# v1.net
KiCad netlist of a schematic drawn in EAGLE
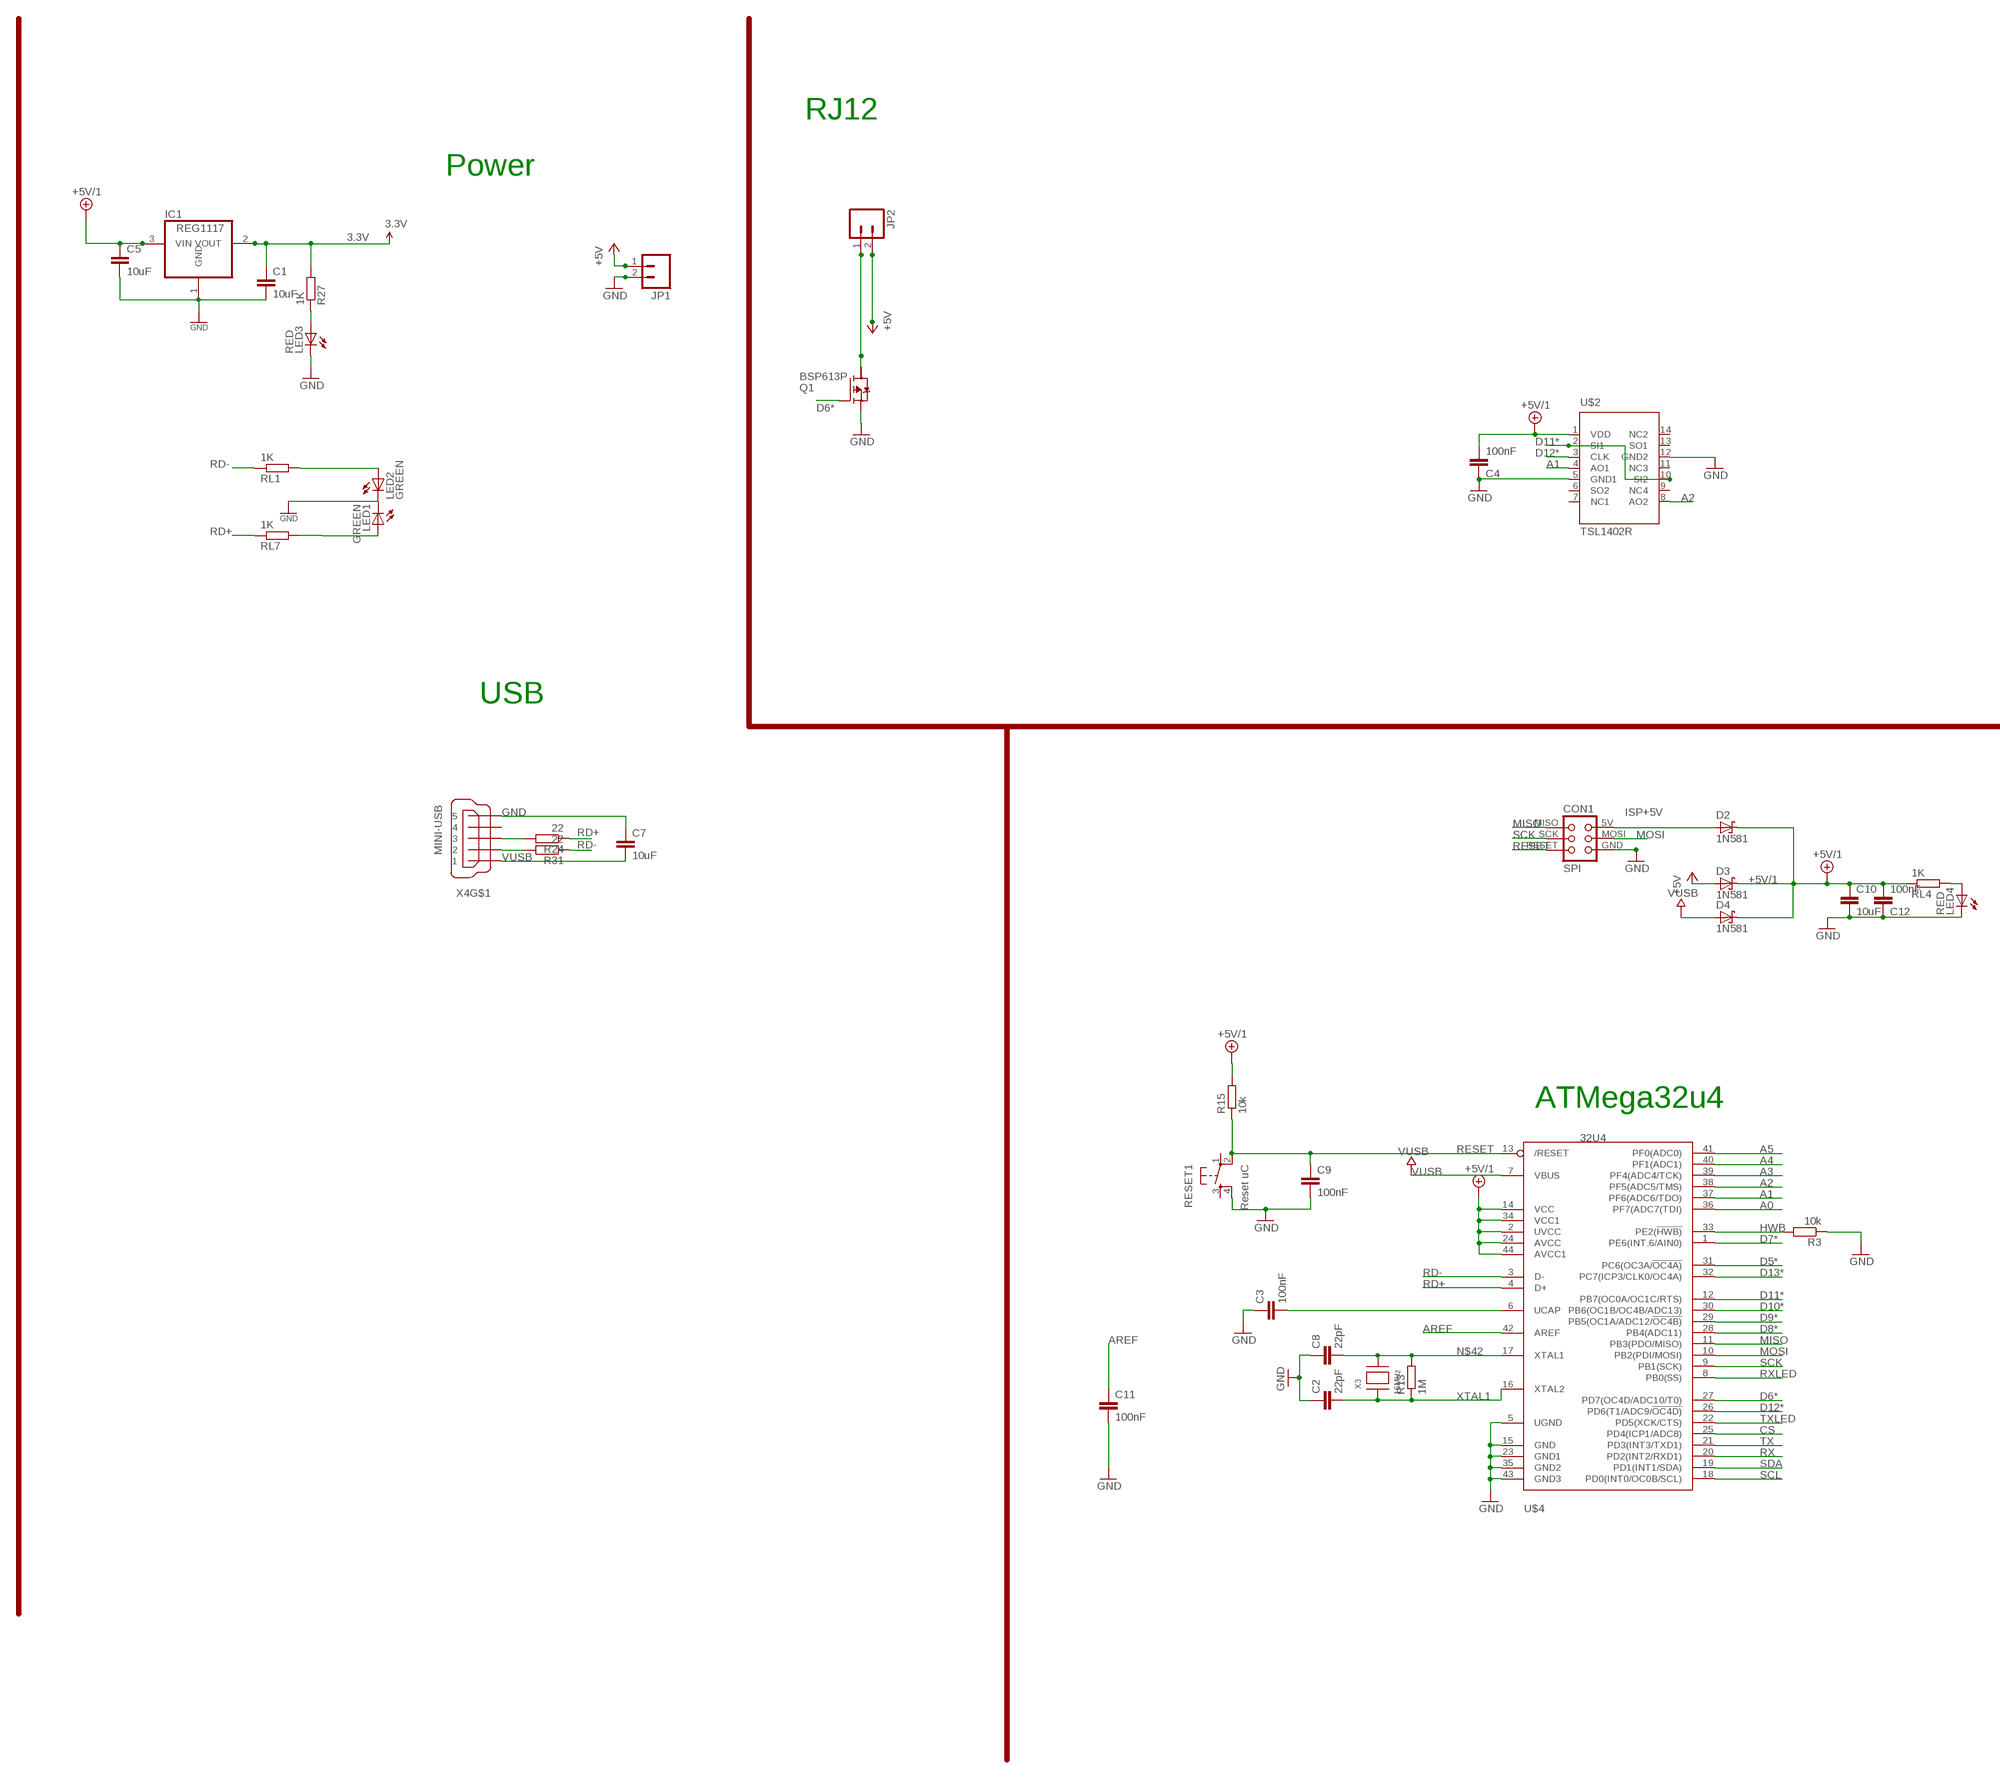
[diagram p0: schematic, sheet 1, part 1 of 2]
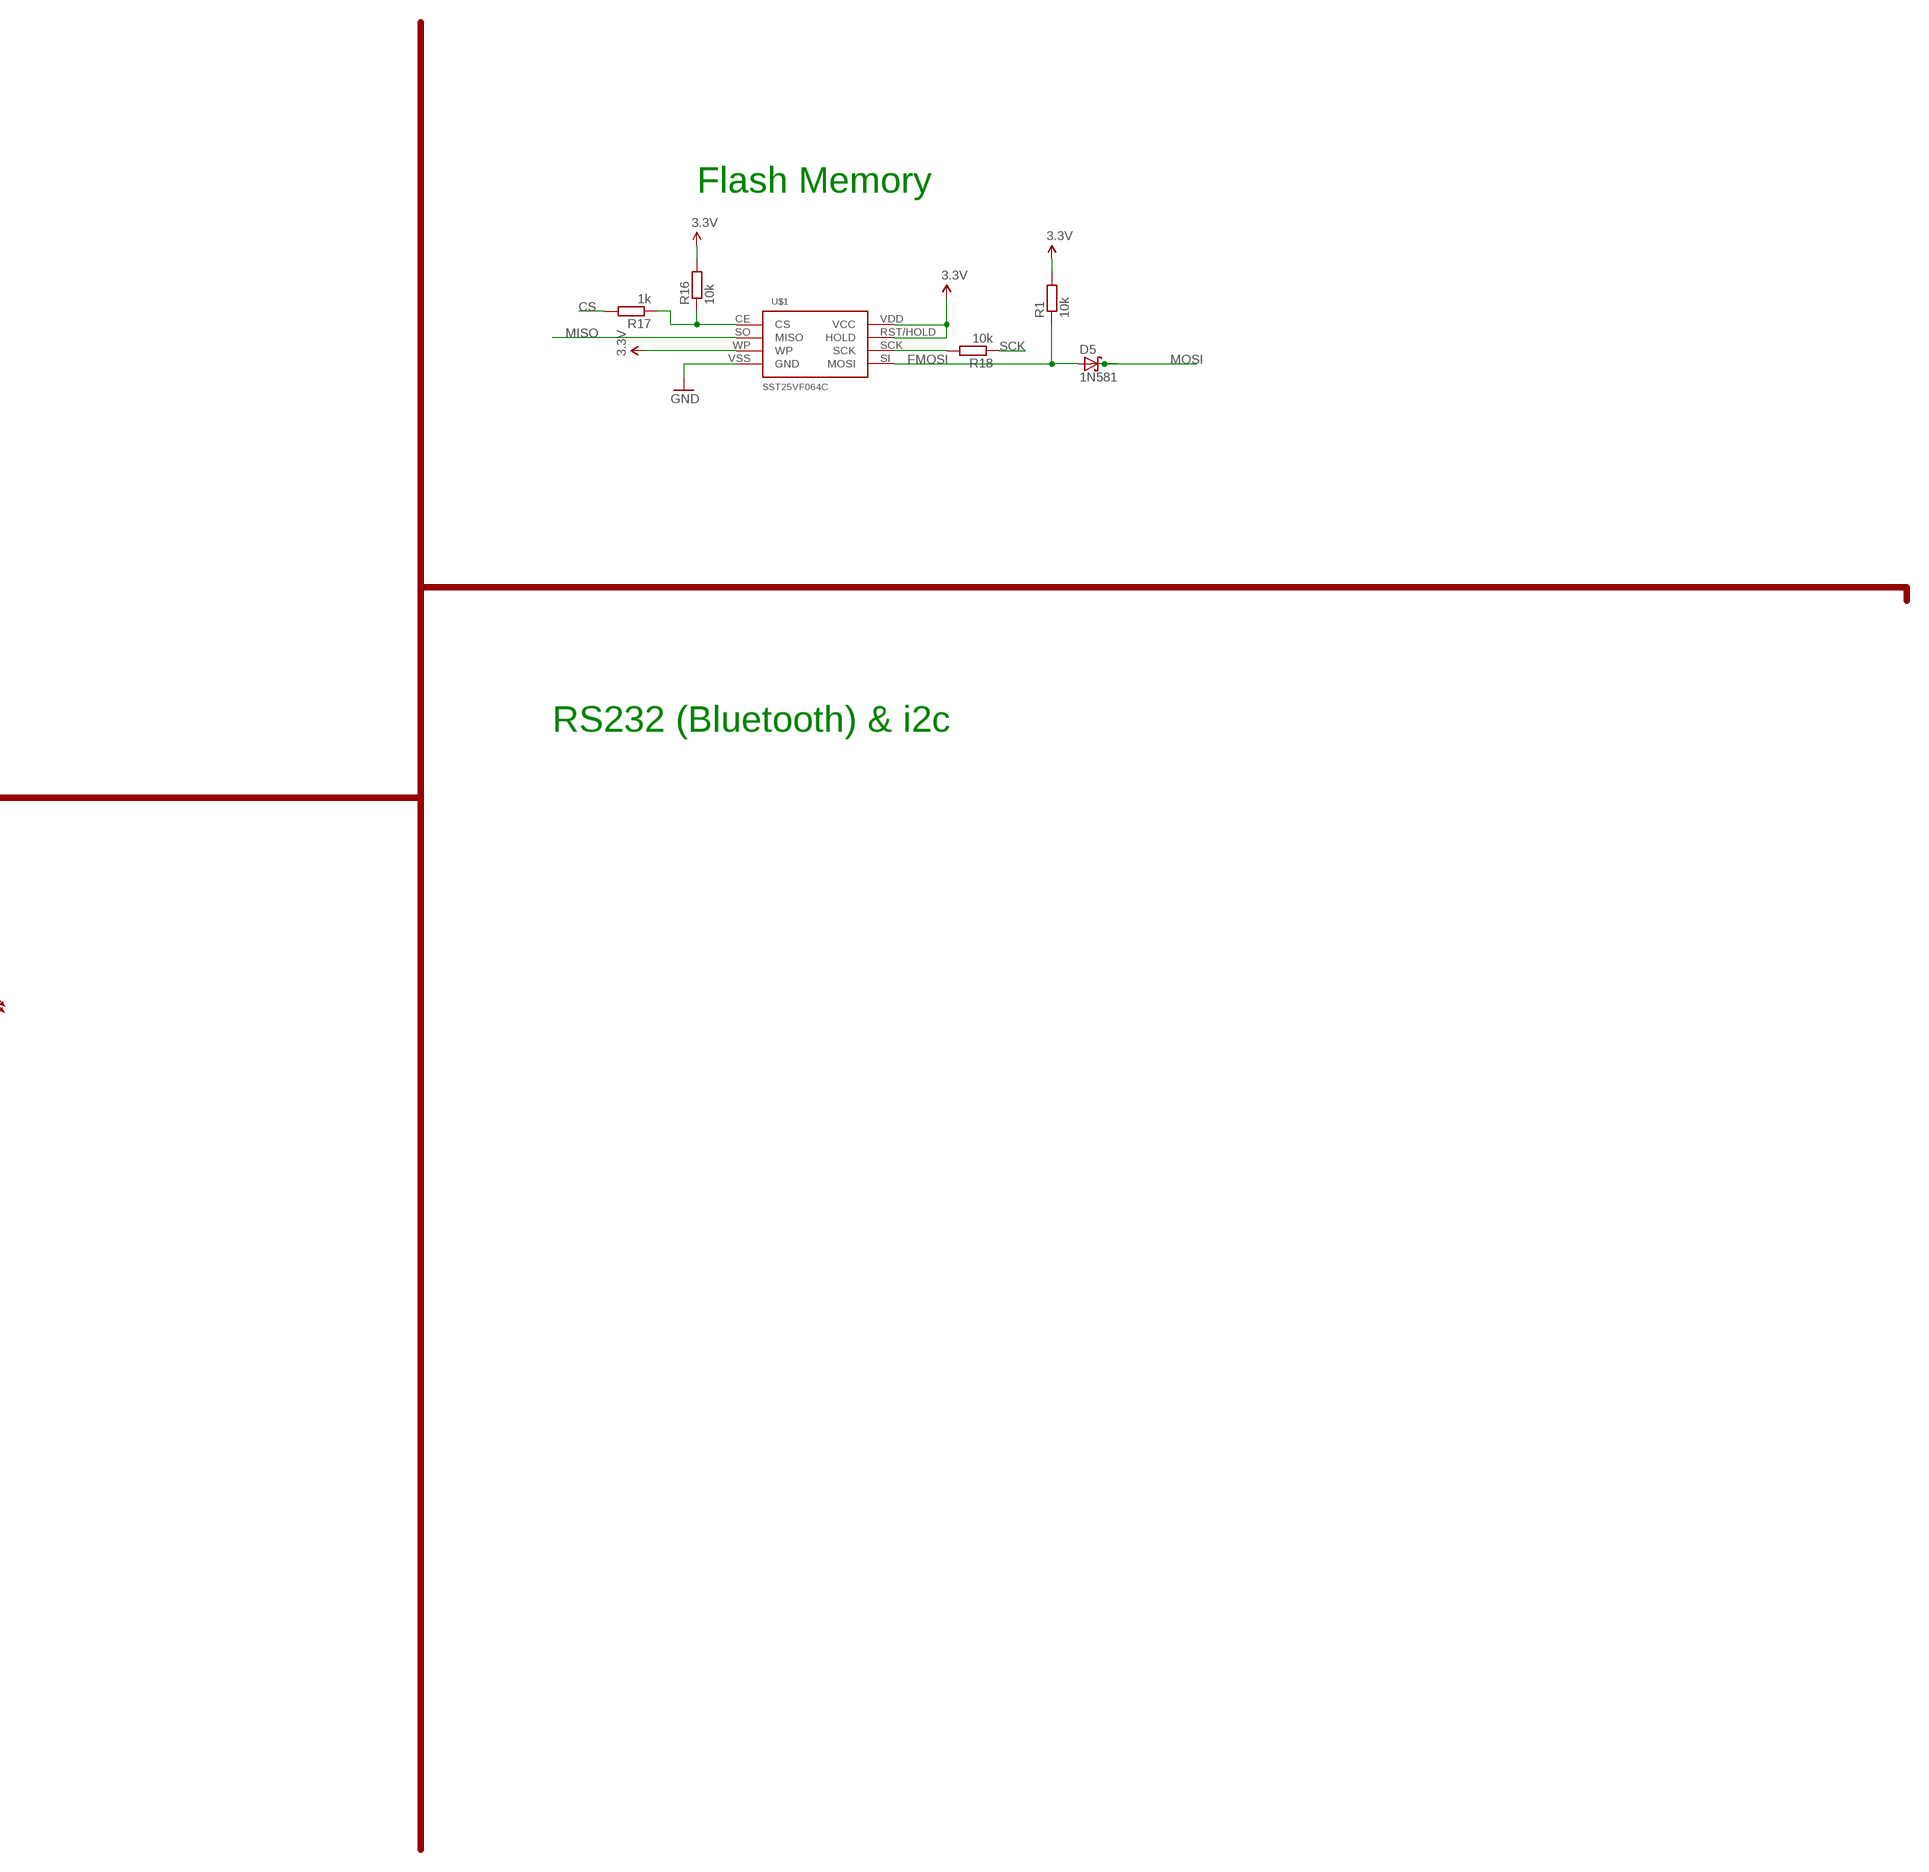
[diagram p1: schematic, sheet 1, part 2 of 2]

(export (version "E")
  (design (tool "Eeschema 10.0.6"))
  (components
    (comp (ref "C1")
      (value "10uF")
      (footprint "eagle-import:C1206")
      (libsource (lib "eagle-import") (part "C-EUC1206"))
    )
    (comp (ref "C2")
      (value "22pF")
      (footprint "eagle-import:C1206")
      (libsource (lib "eagle-import") (part "C-EUC1206"))
    )
    (comp (ref "C3")
      (value "100nF")
      (footprint "eagle-import:C1206")
      (libsource (lib "eagle-import") (part "C-EUC1206"))
    )
    (comp (ref "C4")
      (value "100nF")
      (footprint "eagle-import:C1206")
      (libsource (lib "eagle-import") (part "C-EUC1206"))
    )
    (comp (ref "C5")
      (value "10uF")
      (footprint "eagle-import:C1206")
      (libsource (lib "eagle-import") (part "C-EUC1206"))
    )
    (comp (ref "C7")
      (value "10uF")
      (footprint "eagle-import:C1206")
      (libsource (lib "eagle-import") (part "C-EUC1206"))
    )
    (comp (ref "C8")
      (value "22pF")
      (footprint "eagle-import:C1206")
      (libsource (lib "eagle-import") (part "C-EUC1206"))
    )
    (comp (ref "C9")
      (value "100nF")
      (footprint "eagle-import:C1206")
      (libsource (lib "eagle-import") (part "C-EUC1206"))
    )
    (comp (ref "C10")
      (value "10uF")
      (footprint "eagle-import:C1206")
      (libsource (lib "eagle-import") (part "C-EUC1206"))
    )
    (comp (ref "C11")
      (value "100nF")
      (footprint "eagle-import:C1206")
      (libsource (lib "eagle-import") (part "C-EUC1206"))
    )
    (comp (ref "C12")
      (value "100nF")
      (footprint "eagle-import:C1206")
      (libsource (lib "eagle-import") (part "C-EUC1206"))
    )
    (comp (ref "CON1")
      (value "SPI")
      (footprint "eagle-import:TC2030-MCP-NL")
      (libsource (lib "eagle-import") (part "TINYISPT"))
    )
    (comp (ref "D2")
      (value "1N581")
      (footprint "eagle-import:LED-1206")
      (libsource (lib "eagle-import") (part "1N581D1206"))
    )
    (comp (ref "D3")
      (value "1N581")
      (footprint "eagle-import:LED-1206")
      (libsource (lib "eagle-import") (part "1N581D1206"))
    )
    (comp (ref "D4")
      (value "1N581")
      (footprint "eagle-import:LED-1206")
      (libsource (lib "eagle-import") (part "1N581D1206"))
    )
    (comp (ref "D5")
      (value "1N581")
      (footprint "eagle-import:LED-1206")
      (libsource (lib "eagle-import") (part "1N581D1206"))
    )
    (comp (ref "IC1")
      (value "REG1117")
      (footprint "eagle-import:SOT223")
      (libsource (lib "eagle-import") (part "REG1117"))
    )
    (comp (ref "JP1")
      (value "M02LOCK_LONGPADS")
      (footprint "eagle-import:1X02_LOCK_LONGPADS")
      (libsource (lib "eagle-import") (part "M02LOCK_LONGPADS"))
    )
    (comp (ref "JP2")
      (value "M02LOCK_LONGPADS")
      (footprint "eagle-import:1X02_LOCK_LONGPADS")
      (libsource (lib "eagle-import") (part "M02LOCK_LONGPADS"))
    )
    (comp (ref "LED1")
      (value "GREEN")
      (footprint "eagle-import:CHIP-LED0805")
      (libsource (lib "eagle-import") (part "LEDCHIP-LED0805"))
    )
    (comp (ref "LED2")
      (value "GREEN")
      (footprint "eagle-import:CHIP-LED0805")
      (libsource (lib "eagle-import") (part "LEDCHIP-LED0805"))
    )
    (comp (ref "LED3")
      (value "RED")
      (footprint "eagle-import:CHIP-LED0805")
      (libsource (lib "eagle-import") (part "LEDCHIP-LED0805"))
    )
    (comp (ref "LED4")
      (value "RED")
      (footprint "eagle-import:CHIP-LED0805")
      (libsource (lib "eagle-import") (part "LEDCHIP-LED0805"))
    )
    (comp (ref "Q1")
      (value "BSP613P")
      (footprint "eagle-import:PG-SOT-223")
      (libsource (lib "eagle-import") (part "BSP613P"))
    )
    (comp (ref "R1")
      (value "10k")
      (footprint "eagle-import:R1206")
      (libsource (lib "eagle-import") (part "R-EU_R1206"))
    )
    (comp (ref "R3")
      (value "10k")
      (footprint "eagle-import:M0805")
      (libsource (lib "eagle-import") (part "resistor_R-EU_M0805"))
    )
    (comp (ref "R13")
      (value "1M")
      (footprint "eagle-import:R1206")
      (libsource (lib "eagle-import") (part "R-EU_R1206"))
    )
    (comp (ref "R15")
      (value "10k")
      (footprint "eagle-import:M0805")
      (libsource (lib "eagle-import") (part "resistor_R-EU_M0805"))
    )
    (comp (ref "R16")
      (value "10k")
      (footprint "eagle-import:R1206")
      (libsource (lib "eagle-import") (part "R-EU_R1206"))
    )
    (comp (ref "R17")
      (value "1k")
      (footprint "eagle-import:R0805")
      (libsource (lib "eagle-import") (part "R-EU_R0805"))
    )
    (comp (ref "R18")
      (value "10k")
      (footprint "eagle-import:R1206")
      (libsource (lib "eagle-import") (part "R-EU_R1206"))
    )
    (comp (ref "R24")
      (value "22")
      (footprint "eagle-import:M1206")
      (libsource (lib "eagle-import") (part "resistor_R-EU_M1206"))
    )
    (comp (ref "R27")
      (value "1K")
      (footprint "eagle-import:R0805")
      (libsource (lib "eagle-import") (part "R-EU_R0805"))
    )
    (comp (ref "R31")
      (value "22")
      (footprint "eagle-import:M1206")
      (libsource (lib "eagle-import") (part "resistor_R-EU_M1206"))
    )
    (comp (ref "RESET1")
      (value "Reset uC")
      (footprint "eagle-import:TACTILE_SWITCH_SMD")
      (libsource (lib "eagle-import") (part "TAC_SWITCHSMD"))
    )
    (comp (ref "RL1")
      (value "1K")
      (footprint "eagle-import:R0805")
      (libsource (lib "eagle-import") (part "R-EU_R0805"))
    )
    (comp (ref "RL4")
      (value "1K")
      (footprint "eagle-import:R0805")
      (libsource (lib "eagle-import") (part "resistor_R-EU_R0805"))
    )
    (comp (ref "RL7")
      (value "1K")
      (footprint "eagle-import:R0805")
      (libsource (lib "eagle-import") (part "R-EU_R0805"))
    )
    (comp (ref "U$1")
      (value "SST25VF064C")
      (footprint "eagle-import:SOIC_8-LEAD")
      (libsource (lib "eagle-import") (part "SST25VF064C"))
    )
    (comp (ref "U$2")
      (value "TSL1402R")
      (footprint "eagle-import:DIL14")
      (libsource (lib "eagle-import") (part "TSL1402R"))
    )
    (comp (ref "U$4")
      (value "32U4")
      (footprint "eagle-import:TQFP44")
      (libsource (lib "eagle-import") (part "ATMEGA32U4-AU"))
    )
    (comp (ref "X3")
      (value "16MHz")
      (footprint "eagle-import:NX6035")
      (libsource (lib "eagle-import") (part "XTALNX6035"))
    )
    (comp (ref "X4")
      (value "MINI-USB")
      (footprint "eagle-import:32005-201")
      (libsource (lib "eagle-import") (part "MINI-USB-SCHIELD-32005-201"))
    )
  )
  (nets
    (net (code "1") (name "+5V") (class "Default")
      (node (ref "D3") (pin "A") (pinfunction "A_A") (pintype "passive"))
      (node (ref "JP1") (pin "1") (pinfunction "1_1") (pintype "passive"))
      (node (ref "JP2") (pin "2") (pinfunction "2_2") (pintype "passive"))
    )
    (net (code "2") (name "+5V{slash}1") (class "Default")
      (node (ref "C10") (pin "1") (pinfunction "1_1") (pintype "passive"))
      (node (ref "C12") (pin "2") (pinfunction "2_2") (pintype "passive"))
      (node (ref "C4") (pin "2") (pinfunction "2_2") (pintype "passive"))
      (node (ref "C5") (pin "1") (pinfunction "1_1") (pintype "passive"))
      (node (ref "D2") (pin "C") (pinfunction "C_C") (pintype "passive"))
      (node (ref "D3") (pin "C") (pinfunction "C_C") (pintype "passive"))
      (node (ref "D4") (pin "C") (pinfunction "C_C") (pintype "passive"))
      (node (ref "IC1") (pin "3") (pinfunction "VIN_3") (pintype "input"))
      (node (ref "R15") (pin "2") (pinfunction "2_2") (pintype "passive"))
      (node (ref "RL4") (pin "1") (pinfunction "1_1") (pintype "passive"))
      (node (ref "U$2") (pin "1") (pinfunction "VDD_1") (pintype "power_in"))
      (node (ref "U$4") (pin "14") (pinfunction "VCC_14") (pintype "bidirectional"))
      (node (ref "U$4") (pin "2") (pinfunction "UVCC_2") (pintype "bidirectional"))
      (node (ref "U$4") (pin "24") (pinfunction "AVCC_24") (pintype "bidirectional"))
      (node (ref "U$4") (pin "34") (pinfunction "VCC1_34") (pintype "bidirectional"))
      (node (ref "U$4") (pin "44") (pinfunction "AVCC1_44") (pintype "bidirectional"))
    )
    (net (code "3") (name "/A0") (class "Default")
      (node (ref "U$4") (pin "36") (pinfunction "PF7(ADC7(TDI)_36") (pintype "bidirectional"))
    )
    (net (code "4") (name "/A1") (class "Default")
      (node (ref "U$2") (pin "4") (pinfunction "AO1_4") (pintype "output"))
      (node (ref "U$4") (pin "37") (pinfunction "PF6(ADC6/TDO)_37") (pintype "bidirectional"))
    )
    (net (code "5") (name "/A2") (class "Default")
      (node (ref "U$2") (pin "8") (pinfunction "AO2_8") (pintype "output"))
      (node (ref "U$4") (pin "38") (pinfunction "PF5(ADC5/TMS)_38") (pintype "bidirectional"))
    )
    (net (code "6") (name "/A3") (class "Default")
      (node (ref "U$4") (pin "39") (pinfunction "PF4(ADC4/TCK)_39") (pintype "bidirectional"))
    )
    (net (code "7") (name "/A4") (class "Default")
      (node (ref "U$4") (pin "40") (pinfunction "PF1(ADC1)_40") (pintype "bidirectional"))
    )
    (net (code "8") (name "/A5") (class "Default")
      (node (ref "U$4") (pin "41") (pinfunction "PF0(ADC0)_41") (pintype "bidirectional"))
    )
    (net (code "9") (name "/AREF") (class "Default")
      (node (ref "C11") (pin "1") (pinfunction "1_1") (pintype "passive"))
      (node (ref "U$4") (pin "42") (pinfunction "AREF_42") (pintype "bidirectional"))
    )
    (net (code "10") (name "/CS") (class "Default")
      (node (ref "R17") (pin "2") (pinfunction "2_2") (pintype "passive"))
      (node (ref "U$4") (pin "25") (pinfunction "PD4(ICP1/ADC8)_25") (pintype "bidirectional"))
    )
    (net (code "11") (name "/D5*") (class "Default")
      (node (ref "U$4") (pin "31") (pinfunction "PC6(OC3A/~{OC4A})_31") (pintype "bidirectional"))
    )
    (net (code "12") (name "/D6*") (class "Default")
      (node (ref "Q1") (pin "1") (pinfunction "G_1") (pintype "passive"))
      (node (ref "U$4") (pin "27") (pinfunction "PD7(OC4D/ADC10/T0)_27") (pintype "bidirectional"))
    )
    (net (code "13") (name "/D7*") (class "Default")
      (node (ref "U$4") (pin "1") (pinfunction "PE6(INT.6/AIN0)_1") (pintype "bidirectional"))
    )
    (net (code "14") (name "/D8*") (class "Default")
      (node (ref "U$4") (pin "28") (pinfunction "PB4(ADC11)_28") (pintype "bidirectional"))
    )
    (net (code "15") (name "/D9*") (class "Default")
      (node (ref "U$4") (pin "29") (pinfunction "PB5(OC1A/ADC12/~{OC4B})_29") (pintype "bidirectional"))
    )
    (net (code "16") (name "/D10*") (class "Default")
      (node (ref "U$4") (pin "30") (pinfunction "PB6(OC1B/OC4B/ADC13)_30") (pintype "bidirectional"))
    )
    (net (code "17") (name "/D11*") (class "Default")
      (node (ref "U$2") (pin "10") (pinfunction "SI2_10") (pintype "input"))
      (node (ref "U$2") (pin "2") (pinfunction "SI1_2") (pintype "input"))
      (node (ref "U$4") (pin "12") (pinfunction "PB7(OC0A/OC1C/RTS)_12") (pintype "bidirectional"))
    )
    (net (code "18") (name "/D12*") (class "Default")
      (node (ref "U$2") (pin "3") (pinfunction "CLK_3") (pintype "input"))
      (node (ref "U$4") (pin "26") (pinfunction "PD6(T1/ADC9/~{OC4D})_26") (pintype "bidirectional"))
    )
    (net (code "19") (name "/D13*") (class "Default")
      (node (ref "U$4") (pin "32") (pinfunction "PC7(ICP3/CLK0/OC4A)_32") (pintype "bidirectional"))
    )
    (net (code "20") (name "/FMOSI") (class "Default")
      (node (ref "D5") (pin "A") (pinfunction "A_A") (pintype "passive"))
      (node (ref "R1") (pin "1") (pinfunction "1_1") (pintype "passive"))
      (node (ref "U$1") (pin "SI") (pinfunction "MOSI_SI") (pintype "bidirectional"))
    )
    (net (code "21") (name "/HWB") (class "Default")
      (node (ref "R3") (pin "2") (pinfunction "2_2") (pintype "passive"))
      (node (ref "U$4") (pin "33") (pinfunction "PE2(~{HWB})_33") (pintype "bidirectional"))
    )
    (net (code "22") (name "/ISP+5V") (class "Default")
      (node (ref "CON1") (pin "5V") (pinfunction "VCC_5V") (pintype "passive"))
      (node (ref "D2") (pin "A") (pinfunction "A_A") (pintype "passive"))
    )
    (net (code "23") (name "/MISO") (class "Default")
      (node (ref "CON1") (pin "MISO") (pinfunction "MISO_MISO") (pintype "passive"))
      (node (ref "U$1") (pin "SO") (pinfunction "MISO_SO") (pintype "bidirectional"))
      (node (ref "U$4") (pin "11") (pinfunction "PB3(PDO/MISO)_11") (pintype "bidirectional"))
    )
    (net (code "24") (name "/MOSI") (class "Default")
      (node (ref "CON1") (pin "MOSI") (pinfunction "MOSI_MOSI") (pintype "passive"))
      (node (ref "D5") (pin "C") (pinfunction "C_C") (pintype "passive"))
      (node (ref "U$4") (pin "10") (pinfunction "PB2(PDI/MOSI)_10") (pintype "bidirectional"))
    )
    (net (code "25") (name "/N$42") (class "Default")
      (node (ref "C8") (pin "2") (pinfunction "2_2") (pintype "passive"))
      (node (ref "R13") (pin "2") (pinfunction "2_2") (pintype "passive"))
      (node (ref "U$4") (pin "17") (pinfunction "XTAL1_17") (pintype "bidirectional"))
      (node (ref "X3") (pin "P$2") (pinfunction "P$2_P$2") (pintype "bidirectional"))
    )
    (net (code "26") (name "/RD+") (class "Default")
      (node (ref "R24") (pin "1") (pinfunction "1_1") (pintype "passive"))
      (node (ref "RL7") (pin "1") (pinfunction "1_1") (pintype "passive"))
      (node (ref "U$4") (pin "4") (pinfunction "D+_4") (pintype "bidirectional"))
    )
    (net (code "27") (name "/RD-") (class "Default")
      (node (ref "R31") (pin "1") (pinfunction "1_1") (pintype "passive"))
      (node (ref "RL1") (pin "1") (pinfunction "1_1") (pintype "passive"))
      (node (ref "U$4") (pin "3") (pinfunction "D-_3") (pintype "bidirectional"))
    )
    (net (code "28") (name "/RESET") (class "Default")
      (node (ref "C9") (pin "1") (pinfunction "1_1") (pintype "passive"))
      (node (ref "CON1") (pin "RESET") (pinfunction "RESET_RESET") (pintype "passive"))
      (node (ref "R15") (pin "1") (pinfunction "1_1") (pintype "passive"))
      (node (ref "RESET1") (pin "2") (pinfunction "2_2") (pintype "passive"))
      (node (ref "U$4") (pin "13") (pinfunction "/RESET_13") (pintype "bidirectional"))
    )
    (net (code "29") (name "/RX") (class "Default")
      (node (ref "U$4") (pin "20") (pinfunction "PD2(INT2/RXD1)_20") (pintype "bidirectional"))
    )
    (net (code "30") (name "/RXLED") (class "Default")
      (node (ref "U$4") (pin "8") (pinfunction "PB0(SS)_8") (pintype "bidirectional"))
    )
    (net (code "31") (name "/SCK") (class "Default")
      (node (ref "CON1") (pin "SCK") (pinfunction "SCK_SCK") (pintype "passive"))
      (node (ref "R18") (pin "1") (pinfunction "1_1") (pintype "passive"))
      (node (ref "U$4") (pin "9") (pinfunction "PB1(SCK)_9") (pintype "bidirectional"))
    )
    (net (code "32") (name "/SCL") (class "Default")
      (node (ref "U$4") (pin "18") (pinfunction "PD0(INT0/OC0B/SCL)_18") (pintype "bidirectional"))
    )
    (net (code "33") (name "/SDA") (class "Default")
      (node (ref "U$4") (pin "19") (pinfunction "PD1(INT1/SDA)_19") (pintype "bidirectional"))
    )
    (net (code "34") (name "/TX") (class "Default")
      (node (ref "U$4") (pin "21") (pinfunction "PD3(INT3/TXD1)_21") (pintype "bidirectional"))
    )
    (net (code "35") (name "/TXLED") (class "Default")
      (node (ref "U$4") (pin "22") (pinfunction "PD5(XCK/CTS)_22") (pintype "bidirectional"))
    )
    (net (code "36") (name "/XTAL1") (class "Default")
      (node (ref "C2") (pin "2") (pinfunction "2_2") (pintype "passive"))
      (node (ref "R13") (pin "1") (pinfunction "1_1") (pintype "passive"))
      (node (ref "U$4") (pin "16") (pinfunction "XTAL2_16") (pintype "bidirectional"))
      (node (ref "X3") (pin "P$1") (pinfunction "P$1_P$1") (pintype "bidirectional"))
    )
    (net (code "37") (name "3.3V") (class "Default")
      (node (ref "C1") (pin "1") (pinfunction "1_1") (pintype "passive"))
      (node (ref "IC1") (pin "2") (pinfunction "VOUT_2") (pintype "output"))
      (node (ref "R1") (pin "2") (pinfunction "2_2") (pintype "passive"))
      (node (ref "R16") (pin "2") (pinfunction "2_2") (pintype "passive"))
      (node (ref "R27") (pin "2") (pinfunction "2_2") (pintype "passive"))
      (node (ref "U$1") (pin "RST/HOLD") (pinfunction "HOLD_RST/HOLD") (pintype "bidirectional"))
      (node (ref "U$1") (pin "VDD") (pinfunction "VCC_VDD") (pintype "bidirectional"))
      (node (ref "U$1") (pin "WP") (pinfunction "WP_WP") (pintype "bidirectional"))
    )
    (net (code "38") (name "GND") (class "Default")
      (node (ref "C1") (pin "2") (pinfunction "2_2") (pintype "passive"))
      (node (ref "C10") (pin "2") (pinfunction "2_2") (pintype "passive"))
      (node (ref "C11") (pin "2") (pinfunction "2_2") (pintype "passive"))
      (node (ref "C12") (pin "1") (pinfunction "1_1") (pintype "passive"))
      (node (ref "C2") (pin "1") (pinfunction "1_1") (pintype "passive"))
      (node (ref "C3") (pin "1") (pinfunction "1_1") (pintype "passive"))
      (node (ref "C4") (pin "1") (pinfunction "1_1") (pintype "passive"))
      (node (ref "C5") (pin "2") (pinfunction "2_2") (pintype "passive"))
      (node (ref "C7") (pin "1") (pinfunction "1_1") (pintype "passive"))
      (node (ref "C8") (pin "1") (pinfunction "1_1") (pintype "passive"))
      (node (ref "C9") (pin "2") (pinfunction "2_2") (pintype "passive"))
      (node (ref "CON1") (pin "GND") (pinfunction "GND_GND") (pintype "passive"))
      (node (ref "IC1") (pin "1") (pinfunction "GND_1") (pintype "power_in"))
      (node (ref "JP1") (pin "2") (pinfunction "2_2") (pintype "passive"))
      (node (ref "LED1") (pin "C") (pinfunction "C_C") (pintype "passive"))
      (node (ref "LED2") (pin "C") (pinfunction "C_C") (pintype "passive"))
      (node (ref "LED3") (pin "C") (pinfunction "C_C") (pintype "passive"))
      (node (ref "LED4") (pin "C") (pinfunction "C_C") (pintype "passive"))
      (node (ref "Q1") (pin "3") (pinfunction "S_3") (pintype "passive"))
      (node (ref "R3") (pin "1") (pinfunction "1_1") (pintype "passive"))
      (node (ref "RESET1") (pin "4") (pinfunction "4_4") (pintype "passive"))
      (node (ref "U$1") (pin "VSS") (pinfunction "GND_VSS") (pintype "bidirectional"))
      (node (ref "U$2") (pin "12") (pinfunction "GND2_12") (pintype "power_in"))
      (node (ref "U$2") (pin "5") (pinfunction "GND1_5") (pintype "power_in"))
      (node (ref "U$4") (pin "15") (pinfunction "GND_15") (pintype "bidirectional"))
      (node (ref "U$4") (pin "23") (pinfunction "GND1_23") (pintype "bidirectional"))
      (node (ref "U$4") (pin "35") (pinfunction "GND2_35") (pintype "bidirectional"))
      (node (ref "U$4") (pin "43") (pinfunction "GND3_43") (pintype "bidirectional"))
      (node (ref "U$4") (pin "5") (pinfunction "UGND_5") (pintype "bidirectional"))
      (node (ref "X4") (pin "5") (pinfunction "5_5") (pintype "passive"))
    )
    (net (code "39") (name "Net-(JP2-Pad1)") (class "Default")
      (node (ref "JP2") (pin "1") (pinfunction "1_1") (pintype "passive"))
      (node (ref "Q1") (pin "2") (pinfunction "D_2") (pintype "passive"))
    )
    (net (code "40") (name "Net-(LED1-PadA)") (class "Default")
      (node (ref "LED1") (pin "A") (pinfunction "A_A") (pintype "passive"))
      (node (ref "RL7") (pin "2") (pinfunction "2_2") (pintype "passive"))
    )
    (net (code "41") (name "Net-(LED2-PadA)") (class "Default")
      (node (ref "LED2") (pin "A") (pinfunction "A_A") (pintype "passive"))
      (node (ref "RL1") (pin "2") (pinfunction "2_2") (pintype "passive"))
    )
    (net (code "42") (name "Net-(LED3-PadA)") (class "Default")
      (node (ref "LED3") (pin "A") (pinfunction "A_A") (pintype "passive"))
      (node (ref "R27") (pin "1") (pinfunction "1_1") (pintype "passive"))
    )
    (net (code "43") (name "Net-(LED4-PadA)") (class "Default")
      (node (ref "LED4") (pin "A") (pinfunction "A_A") (pintype "passive"))
      (node (ref "RL4") (pin "2") (pinfunction "2_2") (pintype "passive"))
    )
    (net (code "44") (name "Net-(R18-Pad2)") (class "Default")
      (node (ref "R18") (pin "2") (pinfunction "2_2") (pintype "passive"))
      (node (ref "U$1") (pin "SCK") (pinfunction "SCK_SCK") (pintype "bidirectional"))
    )
    (net (code "45") (name "Net-(R24-Pad2)") (class "Default")
      (node (ref "R24") (pin "2") (pinfunction "2_2") (pintype "passive"))
      (node (ref "X4") (pin "3") (pinfunction "3_3") (pintype "passive"))
    )
    (net (code "46") (name "Net-(R31-Pad2)") (class "Default")
      (node (ref "R31") (pin "2") (pinfunction "2_2") (pintype "passive"))
      (node (ref "X4") (pin "2") (pinfunction "2_2") (pintype "passive"))
    )
    (net (code "47") (name "Net-(U$1-CS)") (class "Default")
      (node (ref "R16") (pin "1") (pinfunction "1_1") (pintype "passive"))
      (node (ref "R17") (pin "1") (pinfunction "1_1") (pintype "passive"))
      (node (ref "U$1") (pin "CE") (pinfunction "CS_CE") (pintype "bidirectional"))
    )
    (net (code "48") (name "Net-(U$4-UCAP)") (class "Default")
      (node (ref "C3") (pin "2") (pinfunction "2_2") (pintype "passive"))
      (node (ref "U$4") (pin "6") (pinfunction "UCAP_6") (pintype "bidirectional"))
    )
    (net (code "49") (name "VUSB") (class "Default")
      (node (ref "C7") (pin "2") (pinfunction "2_2") (pintype "passive"))
      (node (ref "D4") (pin "A") (pinfunction "A_A") (pintype "passive"))
      (node (ref "U$4") (pin "7") (pinfunction "VBUS_7") (pintype "bidirectional"))
      (node (ref "X4") (pin "1") (pinfunction "1_1") (pintype "passive"))
    )
    (net (code "50") (name "unconnected-(Q1-D-Pad4)") (class "Default")
      (node (ref "Q1") (pin "4") (pinfunction "D_4") (pintype "passive"))
    )
    (net (code "51") (name "unconnected-(RESET1-Pad1)") (class "Default")
      (node (ref "RESET1") (pin "1") (pinfunction "1_1") (pintype "passive"))
    )
    (net (code "52") (name "unconnected-(RESET1-Pad3)") (class "Default")
      (node (ref "RESET1") (pin "3") (pinfunction "3_3") (pintype "passive"))
    )
    (net (code "53") (name "unconnected-(U$2-NC1-Pad7)") (class "Default")
      (node (ref "U$2") (pin "7") (pinfunction "NC1_7") (pintype "no_connect"))
    )
    (net (code "54") (name "unconnected-(U$2-NC2-Pad14)") (class "Default")
      (node (ref "U$2") (pin "14") (pinfunction "NC2_14") (pintype "no_connect"))
    )
    (net (code "55") (name "unconnected-(U$2-NC3-Pad11)") (class "Default")
      (node (ref "U$2") (pin "11") (pinfunction "NC3_11") (pintype "no_connect"))
    )
    (net (code "56") (name "unconnected-(U$2-NC4-Pad9)") (class "Default")
      (node (ref "U$2") (pin "9") (pinfunction "NC4_9") (pintype "no_connect"))
    )
    (net (code "57") (name "unconnected-(U$2-SO1-Pad13)") (class "Default")
      (node (ref "U$2") (pin "13") (pinfunction "SO1_13") (pintype "output"))
    )
    (net (code "58") (name "unconnected-(U$2-SO2-Pad6)") (class "Default")
      (node (ref "U$2") (pin "6") (pinfunction "SO2_6") (pintype "output"))
    )
    (net (code "59") (name "unconnected-(X4-Pad4)") (class "Default")
      (node (ref "X4") (pin "4") (pinfunction "4_4") (pintype "passive"))
    )
  )
)
